# smd_can4vscp_rs232_rev_C.net
KiCad netlist of a schematic drawn in EAGLE
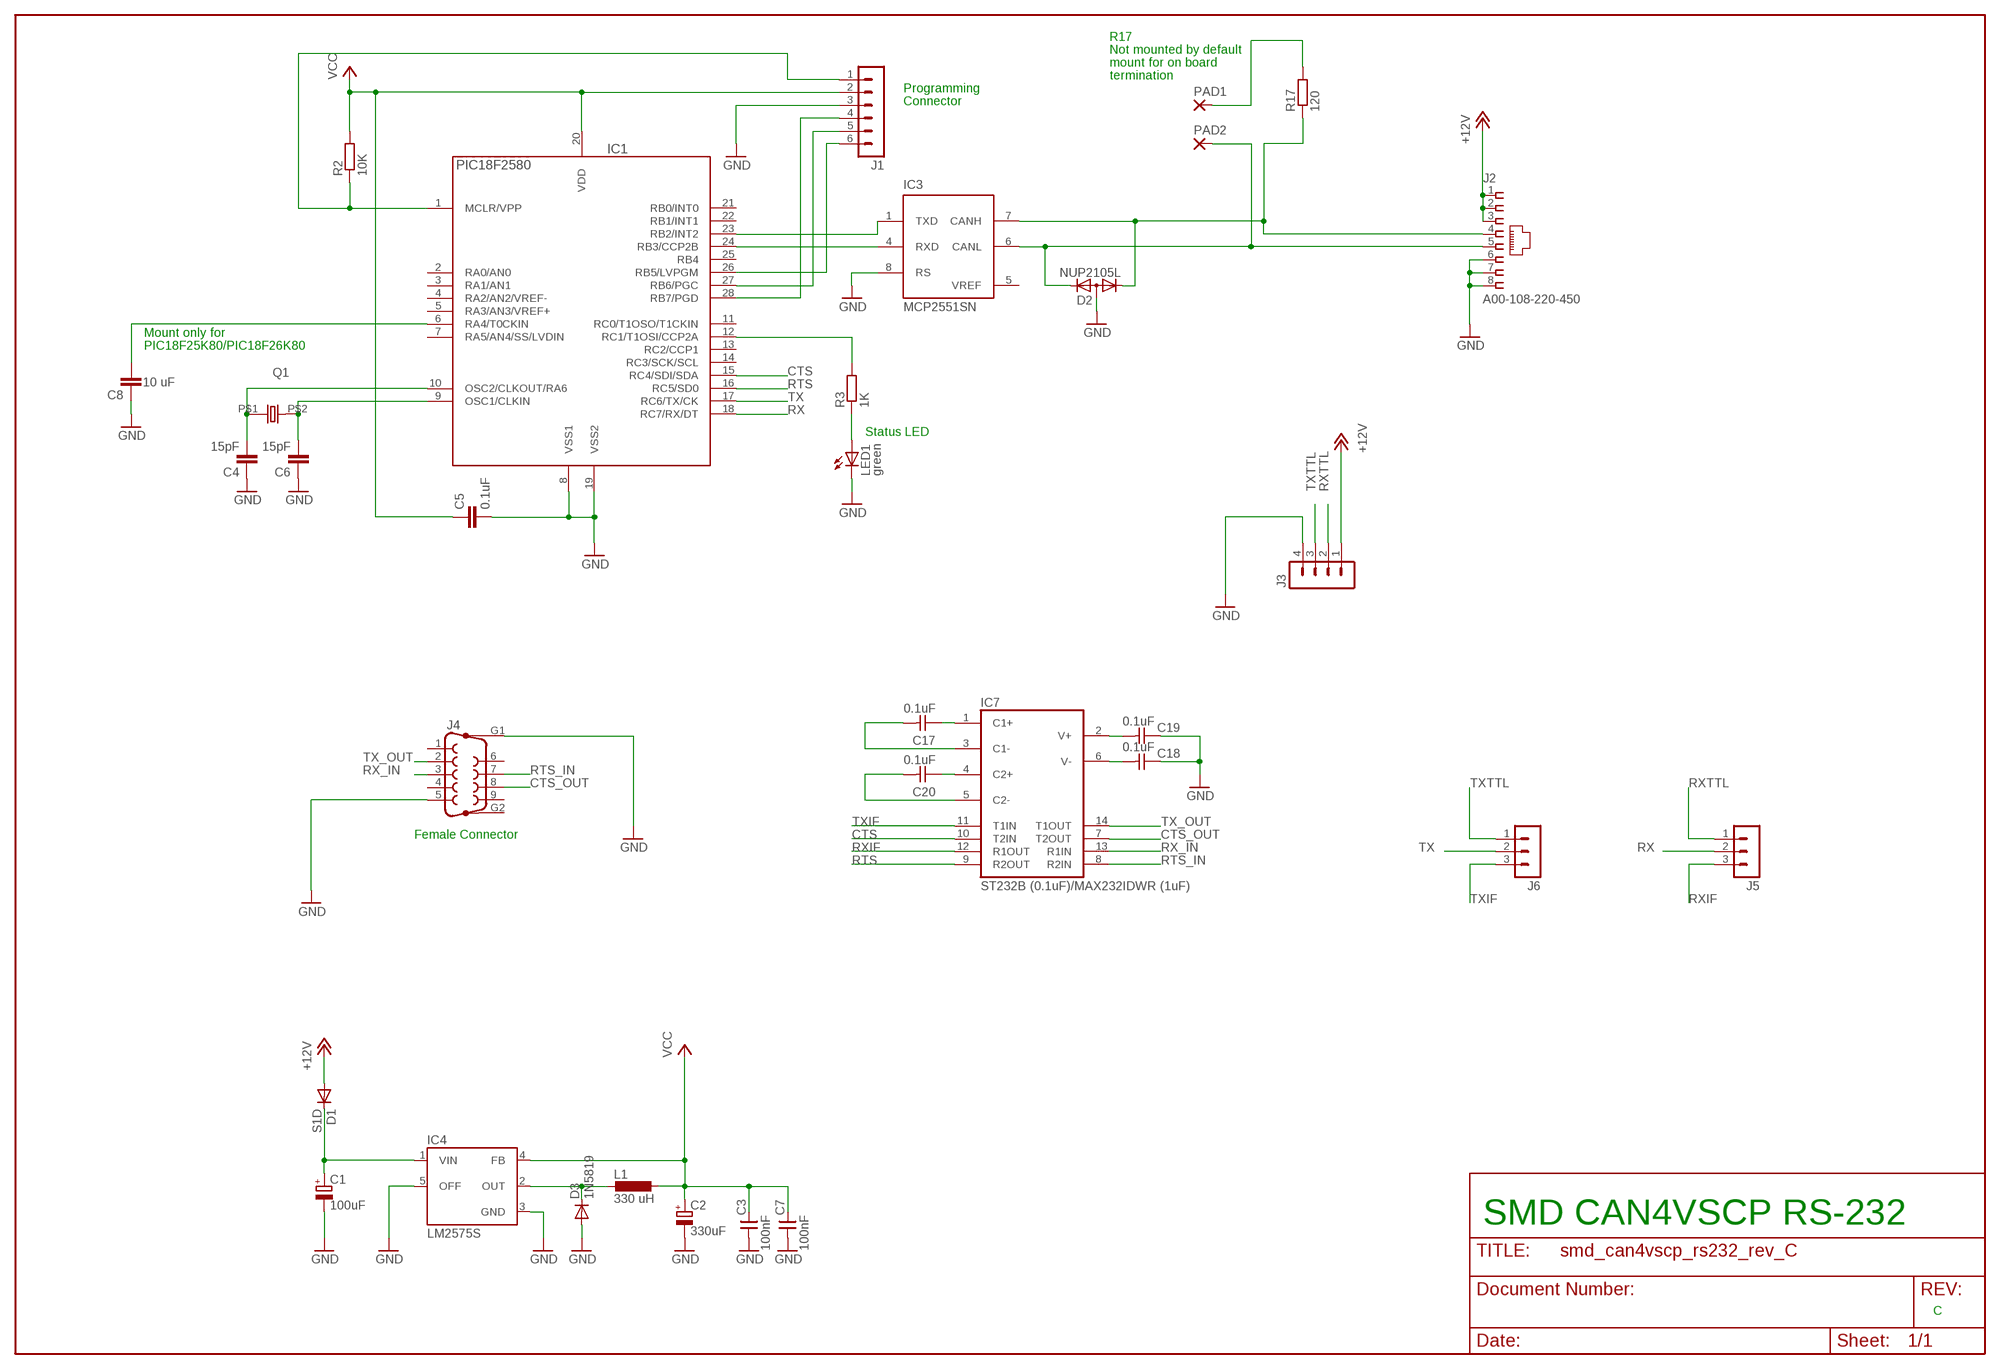
[diagram p0: schematic, sheet 1]

(export (version "E")
  (design (tool "Eeschema 10.0.6"))
  (components
    (comp (ref "C1")
      (value "100uF")
      (footprint "eagle-import:PANASONIC_D")
      (libsource (lib "eagle-import") (part "CPOL-EUD"))
    )
    (comp (ref "C2")
      (value "330uF")
      (footprint "eagle-import:PANASONIC_D")
      (libsource (lib "eagle-import") (part "CPOL-EUD"))
    )
    (comp (ref "C3")
      (value "100nF")
      (footprint "eagle-import:0805")
      (libsource (lib "eagle-import") (part "CNP-0805"))
    )
    (comp (ref "C4")
      (value "15pF")
      (footprint "eagle-import:C0805")
      (libsource (lib "eagle-import") (part "C-EUC0805"))
    )
    (comp (ref "C5")
      (value "0.1uF")
      (footprint "eagle-import:C0805")
      (libsource (lib "eagle-import") (part "C-EUC0805"))
    )
    (comp (ref "C6")
      (value "15pF")
      (footprint "eagle-import:C0805")
      (libsource (lib "eagle-import") (part "C-EUC0805"))
    )
    (comp (ref "C7")
      (value "100nF")
      (footprint "eagle-import:0805")
      (libsource (lib "eagle-import") (part "CNP-0805"))
    )
    (comp (ref "C8")
      (value "10 uF")
      (footprint "eagle-import:C0805")
      (libsource (lib "eagle-import") (part "C-EUC0805"))
    )
    (comp (ref "C17")
      (value "0.1uF")
      (footprint "eagle-import:C0805")
      (libsource (lib "eagle-import") (part "NP_CAP0805"))
    )
    (comp (ref "C18")
      (value "0.1uF")
      (footprint "eagle-import:C0805")
      (libsource (lib "eagle-import") (part "NP_CAP0805"))
    )
    (comp (ref "C19")
      (value "0.1uF")
      (footprint "eagle-import:C0805")
      (libsource (lib "eagle-import") (part "NP_CAP0805"))
    )
    (comp (ref "C20")
      (value "0.1uF")
      (footprint "eagle-import:C0805")
      (libsource (lib "eagle-import") (part "NP_CAP0805"))
    )
    (comp (ref "D1")
      (value "S1D")
      (footprint "eagle-import:SOD123")
      (libsource (lib "eagle-import") (part "DIODE-SOD123"))
    )
    (comp (ref "D2")
      (value "NUP2105L")
      (footprint "eagle-import:SOT23")
      (libsource (lib "eagle-import") (part "DIODE-2CA|ACSOT23"))
    )
    (comp (ref "D3")
      (value "1N5819")
      (footprint "eagle-import:SOD123")
      (libsource (lib "eagle-import") (part "DIODE-SOD123"))
    )
    (comp (ref "IC1")
      (value "PIC18F2580")
      (footprint "eagle-import:SO28")
      (libsource (lib "eagle-import") (part "PIC18F252-?I/SOL"))
    )
    (comp (ref "IC3")
      (value "MCP2551SN")
      (footprint "eagle-import:SO-08")
      (libsource (lib "eagle-import") (part "MCP2551SN"))
    )
    (comp (ref "IC4")
      (value "LM2575S")
      (footprint "eagle-import:TO263-5")
      (libsource (lib "eagle-import") (part "LM2575S"))
    )
    (comp (ref "IC7")
      (value "ST232B (0.1uF)/MAX232IDWR (1uF)")
      (footprint "eagle-import:SO16L")
      (libsource (lib "eagle-import") (part "MAX232ECWE"))
    )
    (comp (ref "J1")
      (value "MA06-1")
      (footprint "eagle-import:MA06-1")
      (libsource (lib "eagle-import") (part "MA06-1"))
    )
    (comp (ref "J2")
      (value "A00-108-220-450")
      (footprint "eagle-import:RJ-45")
      (libsource (lib "eagle-import") (part "A00-108-220-450"))
    )
    (comp (ref "J3")
      (value "MA04-1")
      (footprint "eagle-import:MA04-1")
      (libsource (lib "eagle-import") (part "MA04-1"))
    )
    (comp (ref "J4")
      (value "F09HP")
      (footprint "eagle-import:F09HP")
      (libsource (lib "eagle-import") (part "F09HP"))
    )
    (comp (ref "J5")
      (value "MA03-1")
      (footprint "eagle-import:MA03-1")
      (libsource (lib "eagle-import") (part "MA03-1"))
    )
    (comp (ref "J6")
      (value "MA03-1")
      (footprint "eagle-import:MA03-1")
      (libsource (lib "eagle-import") (part "MA03-1"))
    )
    (comp (ref "L1")
      (value "330 uH")
      (footprint "eagle-import:DO3316P")
      (libsource (lib "eagle-import") (part "DO3316P"))
    )
    (comp (ref "LED1")
      (value "green")
      (footprint "eagle-import:CHIPLED_0805")
      (libsource (lib "eagle-import") (part "LEDCHIPLED_0805"))
    )
    (comp (ref "PAD1")
      (value "1,6/0,8")
      (footprint "eagle-import:1,6_0,8")
      (libsource (lib "eagle-import") (part "1,6/0,8"))
    )
    (comp (ref "PAD2")
      (value "1,6/0,8")
      (footprint "eagle-import:1,6_0,8")
      (libsource (lib "eagle-import") (part "1,6/0,8"))
    )
    (comp (ref "Q1")
      (value "HC-49S")
      (footprint "eagle-import:9C")
      (libsource (lib "eagle-import") (part "HC-49S"))
    )
    (comp (ref "R2")
      (value "10K")
      (footprint "eagle-import:R0805")
      (libsource (lib "eagle-import") (part "R-EU_R0805"))
    )
    (comp (ref "R3")
      (value "1K")
      (footprint "eagle-import:R0805")
      (libsource (lib "eagle-import") (part "R-EU_R0805"))
    )
    (comp (ref "R17")
      (value "120")
      (footprint "eagle-import:R0805")
      (libsource (lib "eagle-import") (part "R-EU_R0805"))
    )
  )
  (nets
    (net (code "1") (name "+12V") (class "Default")
      (node (ref "D1") (pin "A") (pinfunction "A_A") (pintype "passive"))
      (node (ref "J2") (pin "1") (pinfunction "1_1") (pintype "passive"))
      (node (ref "J2") (pin "2") (pinfunction "2_2") (pintype "passive"))
      (node (ref "J2") (pin "3") (pinfunction "3_3") (pintype "passive"))
      (node (ref "J3") (pin "1") (pinfunction "1_1") (pintype "passive"))
    )
    (net (code "2") (name "/CTS") (class "Default")
      (node (ref "IC1") (pin "15") (pinfunction "RC4/SDI/SDA_15") (pintype "bidirectional"))
      (node (ref "IC7") (pin "10") (pinfunction "T2IN_10") (pintype "input"))
    )
    (net (code "3") (name "/CTS_OUT") (class "Default")
      (node (ref "IC7") (pin "7") (pinfunction "T2OUT_7") (pintype "output"))
      (node (ref "J4") (pin "8") (pinfunction "8_8") (pintype "passive"))
    )
    (net (code "4") (name "/RTS") (class "Default")
      (node (ref "IC1") (pin "16") (pinfunction "RC5/SD0_16") (pintype "bidirectional"))
      (node (ref "IC7") (pin "9") (pinfunction "R2OUT_9") (pintype "output"))
    )
    (net (code "5") (name "/RTS_IN") (class "Default")
      (node (ref "IC7") (pin "8") (pinfunction "R2IN_8") (pintype "input"))
      (node (ref "J4") (pin "7") (pinfunction "7_7") (pintype "passive"))
    )
    (net (code "6") (name "/RX") (class "Default")
      (node (ref "IC1") (pin "18") (pinfunction "RC7/RX/DT_18") (pintype "bidirectional"))
      (node (ref "J5") (pin "2") (pinfunction "2_2") (pintype "passive"))
    )
    (net (code "7") (name "/RXIF") (class "Default")
      (node (ref "IC7") (pin "12") (pinfunction "R1OUT_12") (pintype "output"))
      (node (ref "J5") (pin "3") (pinfunction "3_3") (pintype "passive"))
    )
    (net (code "8") (name "/RXTTL") (class "Default")
      (node (ref "J3") (pin "2") (pinfunction "2_2") (pintype "passive"))
      (node (ref "J5") (pin "1") (pinfunction "1_1") (pintype "passive"))
    )
    (net (code "9") (name "/RX_IN") (class "Default")
      (node (ref "IC7") (pin "13") (pinfunction "R1IN_13") (pintype "input"))
      (node (ref "J4") (pin "3") (pinfunction "3_3") (pintype "passive"))
    )
    (net (code "10") (name "/TX") (class "Default")
      (node (ref "IC1") (pin "17") (pinfunction "RC6/TX/CK_17") (pintype "bidirectional"))
      (node (ref "J6") (pin "2") (pinfunction "2_2") (pintype "passive"))
    )
    (net (code "11") (name "/TXIF") (class "Default")
      (node (ref "IC7") (pin "11") (pinfunction "T1IN_11") (pintype "input"))
      (node (ref "J6") (pin "3") (pinfunction "3_3") (pintype "passive"))
    )
    (net (code "12") (name "/TXTTL") (class "Default")
      (node (ref "J3") (pin "3") (pinfunction "3_3") (pintype "passive"))
      (node (ref "J6") (pin "1") (pinfunction "1_1") (pintype "passive"))
    )
    (net (code "13") (name "/TX_OUT") (class "Default")
      (node (ref "IC7") (pin "14") (pinfunction "T1OUT_14") (pintype "output"))
      (node (ref "J4") (pin "2") (pinfunction "2_2") (pintype "passive"))
    )
    (net (code "14") (name "/VREF") (class "Default")
      (node (ref "IC3") (pin "5") (pinfunction "VREF_5") (pintype "power_in"))
    )
    (net (code "15") (name "GND") (class "Default")
      (node (ref "C1") (pin "-") (pinfunction "-_-") (pintype "passive"))
      (node (ref "C18") (pin "1") (pinfunction "1_1") (pintype "passive"))
      (node (ref "C19") (pin "1") (pinfunction "1_1") (pintype "passive"))
      (node (ref "C2") (pin "-") (pinfunction "-_-") (pintype "passive"))
      (node (ref "C3") (pin "1") (pinfunction "1_1") (pintype "passive"))
      (node (ref "C4") (pin "1") (pinfunction "1_1") (pintype "passive"))
      (node (ref "C5") (pin "2") (pinfunction "2_2") (pintype "passive"))
      (node (ref "C6") (pin "1") (pinfunction "1_1") (pintype "passive"))
      (node (ref "C7") (pin "1") (pinfunction "1_1") (pintype "passive"))
      (node (ref "C8") (pin "1") (pinfunction "1_1") (pintype "passive"))
      (node (ref "D2") (pin "3") (pinfunction "A_3") (pintype "passive"))
      (node (ref "D3") (pin "A") (pinfunction "A_A") (pintype "passive"))
      (node (ref "IC1") (pin "19") (pinfunction "VSS2_19") (pintype "power_in"))
      (node (ref "IC1") (pin "8") (pinfunction "VSS1_8") (pintype "power_in"))
      (node (ref "IC3") (pin "8") (pinfunction "RS_8") (pintype "input"))
      (node (ref "IC4") (pin "3") (pinfunction "GND_3") (pintype "power_in"))
      (node (ref "IC4") (pin "5") (pinfunction "OFF_5") (pintype "input"))
      (node (ref "J1") (pin "3") (pinfunction "3_3") (pintype "passive"))
      (node (ref "J2") (pin "6") (pinfunction "6_6") (pintype "passive"))
      (node (ref "J2") (pin "7") (pinfunction "7_7") (pintype "passive"))
      (node (ref "J2") (pin "8") (pinfunction "8_8") (pintype "passive"))
      (node (ref "J3") (pin "4") (pinfunction "4_4") (pintype "passive"))
      (node (ref "J4") (pin "5") (pinfunction "5_5") (pintype "passive"))
      (node (ref "J4") (pin "G1") (pinfunction "G1_G1") (pintype "passive"))
      (node (ref "LED1") (pin "C") (pinfunction "C_C") (pintype "passive"))
    )
    (net (code "16") (name "Net-(D2-K1)") (class "Default")
      (node (ref "D2") (pin "1") (pinfunction "K1_1") (pintype "passive"))
      (node (ref "IC3") (pin "7") (pinfunction "CANH_7") (pintype "bidirectional"))
      (node (ref "J2") (pin "4") (pinfunction "4_4") (pintype "passive"))
      (node (ref "R17") (pin "1") (pinfunction "1_1") (pintype "passive"))
    )
    (net (code "17") (name "Net-(D2-K2)") (class "Default")
      (node (ref "D2") (pin "2") (pinfunction "K2_2") (pintype "passive"))
      (node (ref "IC3") (pin "6") (pinfunction "CANL_6") (pintype "bidirectional"))
      (node (ref "J2") (pin "5") (pinfunction "5_5") (pintype "passive"))
      (node (ref "PAD2") (pin "1") (pinfunction "P_1") (pintype "passive"))
    )
    (net (code "18") (name "Net-(IC1-MCLR{slash}VPP)") (class "Default")
      (node (ref "IC1") (pin "1") (pinfunction "MCLR/VPP_1") (pintype "input"))
      (node (ref "J1") (pin "1") (pinfunction "1_1") (pintype "passive"))
      (node (ref "R2") (pin "1") (pinfunction "1_1") (pintype "passive"))
    )
    (net (code "19") (name "Net-(IC1-OSC1{slash}CLKIN)") (class "Default")
      (node (ref "C6") (pin "2") (pinfunction "2_2") (pintype "passive"))
      (node (ref "IC1") (pin "9") (pinfunction "OSC1/CLKIN_9") (pintype "input"))
      (node (ref "Q1") (pin "P$2") (pinfunction "2_P$2") (pintype "passive"))
    )
    (net (code "20") (name "Net-(IC1-OSC2{slash}CLKOUT{slash}RA6)") (class "Default")
      (node (ref "C4") (pin "2") (pinfunction "2_2") (pintype "passive"))
      (node (ref "IC1") (pin "10") (pinfunction "OSC2/CLKOUT/RA6_10") (pintype "output"))
      (node (ref "Q1") (pin "P$1") (pinfunction "1_P$1") (pintype "passive"))
    )
    (net (code "21") (name "Net-(IC1-RA4{slash}T0CKIN)") (class "Default")
      (node (ref "C8") (pin "2") (pinfunction "2_2") (pintype "passive"))
      (node (ref "IC1") (pin "6") (pinfunction "RA4/T0CKIN_6") (pintype "open_collector"))
    )
    (net (code "22") (name "Net-(IC1-RB2{slash}INT2)") (class "Default")
      (node (ref "IC1") (pin "23") (pinfunction "RB2/INT2_23") (pintype "bidirectional"))
      (node (ref "IC3") (pin "1") (pinfunction "TXD_1") (pintype "input"))
    )
    (net (code "23") (name "Net-(IC1-RB3{slash}CCP2B)") (class "Default")
      (node (ref "IC1") (pin "24") (pinfunction "RB3/CCP2B_24") (pintype "bidirectional"))
      (node (ref "IC3") (pin "4") (pinfunction "RXD_4") (pintype "output"))
    )
    (net (code "24") (name "Net-(IC1-RB5{slash}LVPGM)") (class "Default")
      (node (ref "IC1") (pin "26") (pinfunction "RB5/LVPGM_26") (pintype "bidirectional"))
      (node (ref "J1") (pin "6") (pinfunction "6_6") (pintype "passive"))
    )
    (net (code "25") (name "Net-(IC1-RB6{slash}PGC)") (class "Default")
      (node (ref "IC1") (pin "27") (pinfunction "RB6/PGC_27") (pintype "bidirectional"))
      (node (ref "J1") (pin "5") (pinfunction "5_5") (pintype "passive"))
    )
    (net (code "26") (name "Net-(IC1-RB7{slash}PGD)") (class "Default")
      (node (ref "IC1") (pin "28") (pinfunction "RB7/PGD_28") (pintype "bidirectional"))
      (node (ref "J1") (pin "4") (pinfunction "4_4") (pintype "passive"))
    )
    (net (code "27") (name "Net-(IC1-RC1{slash}T1OSI{slash}CCP2A)") (class "Default")
      (node (ref "IC1") (pin "12") (pinfunction "RC1/T1OSI/CCP2A_12") (pintype "bidirectional"))
      (node (ref "R3") (pin "2") (pinfunction "2_2") (pintype "passive"))
    )
    (net (code "28") (name "Net-(IC4-OUT)") (class "Default")
      (node (ref "D3") (pin "C") (pinfunction "C_C") (pintype "passive"))
      (node (ref "IC4") (pin "2") (pinfunction "OUT_2") (pintype "output"))
      (node (ref "L1") (pin "1") (pinfunction "1_1") (pintype "passive"))
    )
    (net (code "29") (name "Net-(IC4-VIN)") (class "Default")
      (node (ref "C1") (pin "+") (pinfunction "+_+") (pintype "passive"))
      (node (ref "D1") (pin "C") (pinfunction "C_C") (pintype "passive"))
      (node (ref "IC4") (pin "1") (pinfunction "VIN_1") (pintype "power_in"))
    )
    (net (code "30") (name "Net-(IC7A-C1+)") (class "Default")
      (node (ref "C17") (pin "1") (pinfunction "1_1") (pintype "passive"))
      (node (ref "IC7") (pin "1") (pinfunction "C1+_1") (pintype "bidirectional"))
    )
    (net (code "31") (name "Net-(IC7A-C1-)") (class "Default")
      (node (ref "C17") (pin "2") (pinfunction "2_2") (pintype "passive"))
      (node (ref "IC7") (pin "3") (pinfunction "C1-_3") (pintype "bidirectional"))
    )
    (net (code "32") (name "Net-(IC7A-C2+)") (class "Default")
      (node (ref "C20") (pin "1") (pinfunction "1_1") (pintype "passive"))
      (node (ref "IC7") (pin "4") (pinfunction "C2+_4") (pintype "bidirectional"))
    )
    (net (code "33") (name "Net-(IC7A-C2-)") (class "Default")
      (node (ref "C20") (pin "2") (pinfunction "2_2") (pintype "passive"))
      (node (ref "IC7") (pin "5") (pinfunction "C2-_5") (pintype "bidirectional"))
    )
    (net (code "34") (name "Net-(IC7A-V+)") (class "Default")
      (node (ref "C19") (pin "2") (pinfunction "2_2") (pintype "passive"))
      (node (ref "IC7") (pin "2") (pinfunction "V+_2") (pintype "bidirectional"))
    )
    (net (code "35") (name "Net-(IC7A-V-)") (class "Default")
      (node (ref "C18") (pin "2") (pinfunction "2_2") (pintype "passive"))
      (node (ref "IC7") (pin "6") (pinfunction "V-_6") (pintype "bidirectional"))
    )
    (net (code "36") (name "Net-(LED1-PadA)") (class "Default")
      (node (ref "LED1") (pin "A") (pinfunction "A_A") (pintype "passive"))
      (node (ref "R3") (pin "1") (pinfunction "1_1") (pintype "passive"))
    )
    (net (code "37") (name "Net-(PAD1-P)") (class "Default")
      (node (ref "PAD1") (pin "1") (pinfunction "P_1") (pintype "passive"))
      (node (ref "R17") (pin "2") (pinfunction "2_2") (pintype "passive"))
    )
    (net (code "38") (name "VCC") (class "Default")
      (node (ref "C2") (pin "+") (pinfunction "+_+") (pintype "passive"))
      (node (ref "C3") (pin "2") (pinfunction "2_2") (pintype "passive"))
      (node (ref "C5") (pin "1") (pinfunction "1_1") (pintype "passive"))
      (node (ref "C7") (pin "2") (pinfunction "2_2") (pintype "passive"))
      (node (ref "IC1") (pin "20") (pinfunction "VDD_20") (pintype "power_in"))
      (node (ref "IC4") (pin "4") (pinfunction "FB_4") (pintype "input"))
      (node (ref "J1") (pin "2") (pinfunction "2_2") (pintype "passive"))
      (node (ref "L1") (pin "2") (pinfunction "2_2") (pintype "passive"))
      (node (ref "R2") (pin "2") (pinfunction "2_2") (pintype "passive"))
    )
    (net (code "39") (name "unconnected-(IC1-RA0{slash}AN0-Pad2)") (class "Default")
      (node (ref "IC1") (pin "2") (pinfunction "RA0/AN0_2") (pintype "bidirectional"))
    )
    (net (code "40") (name "unconnected-(IC1-RA1{slash}AN1-Pad3)") (class "Default")
      (node (ref "IC1") (pin "3") (pinfunction "RA1/AN1_3") (pintype "bidirectional"))
    )
    (net (code "41") (name "unconnected-(IC1-RA2{slash}AN2{slash}VREF--Pad4)") (class "Default")
      (node (ref "IC1") (pin "4") (pinfunction "RA2/AN2/VREF-_4") (pintype "bidirectional"))
    )
    (net (code "42") (name "unconnected-(IC1-RA3{slash}AN3{slash}VREF+-Pad5)") (class "Default")
      (node (ref "IC1") (pin "5") (pinfunction "RA3/AN3/VREF+_5") (pintype "bidirectional"))
    )
    (net (code "43") (name "unconnected-(IC1-RA5{slash}AN4{slash}SS{slash}LVDIN-Pad7)") (class "Default")
      (node (ref "IC1") (pin "7") (pinfunction "RA5/AN4/SS/LVDIN_7") (pintype "bidirectional"))
    )
    (net (code "44") (name "unconnected-(IC1-RB0{slash}INT0-Pad21)") (class "Default")
      (node (ref "IC1") (pin "21") (pinfunction "RB0/INT0_21") (pintype "bidirectional"))
    )
    (net (code "45") (name "unconnected-(IC1-RB1{slash}INT1-Pad22)") (class "Default")
      (node (ref "IC1") (pin "22") (pinfunction "RB1/INT1_22") (pintype "bidirectional"))
    )
    (net (code "46") (name "unconnected-(IC1-RB4-Pad25)") (class "Default")
      (node (ref "IC1") (pin "25") (pinfunction "RB4_25") (pintype "bidirectional"))
    )
    (net (code "47") (name "unconnected-(IC1-RC0{slash}T1OSO{slash}T1CKIN-Pad11)") (class "Default")
      (node (ref "IC1") (pin "11") (pinfunction "RC0/T1OSO/T1CKIN_11") (pintype "bidirectional"))
    )
    (net (code "48") (name "unconnected-(IC1-RC2{slash}CCP1-Pad13)") (class "Default")
      (node (ref "IC1") (pin "13") (pinfunction "RC2/CCP1_13") (pintype "bidirectional"))
    )
    (net (code "49") (name "unconnected-(IC1-RC3{slash}SCK{slash}SCL-Pad14)") (class "Default")
      (node (ref "IC1") (pin "14") (pinfunction "RC3/SCK/SCL_14") (pintype "bidirectional"))
    )
    (net (code "50") (name "unconnected-(J4-Pad1)") (class "Default")
      (node (ref "J4") (pin "1") (pinfunction "1_1") (pintype "passive"))
    )
    (net (code "51") (name "unconnected-(J4-Pad4)") (class "Default")
      (node (ref "J4") (pin "4") (pinfunction "4_4") (pintype "passive"))
    )
    (net (code "52") (name "unconnected-(J4-Pad6)") (class "Default")
      (node (ref "J4") (pin "6") (pinfunction "6_6") (pintype "passive"))
    )
    (net (code "53") (name "unconnected-(J4-Pad9)") (class "Default")
      (node (ref "J4") (pin "9") (pinfunction "9_9") (pintype "passive"))
    )
    (net (code "54") (name "unconnected-(J4-PadG2)") (class "Default")
      (node (ref "J4") (pin "G2") (pinfunction "G2_G2") (pintype "passive"))
    )
  )
)
